# Sensor_Board.net
KiCad netlist of a schematic drawn in EAGLE
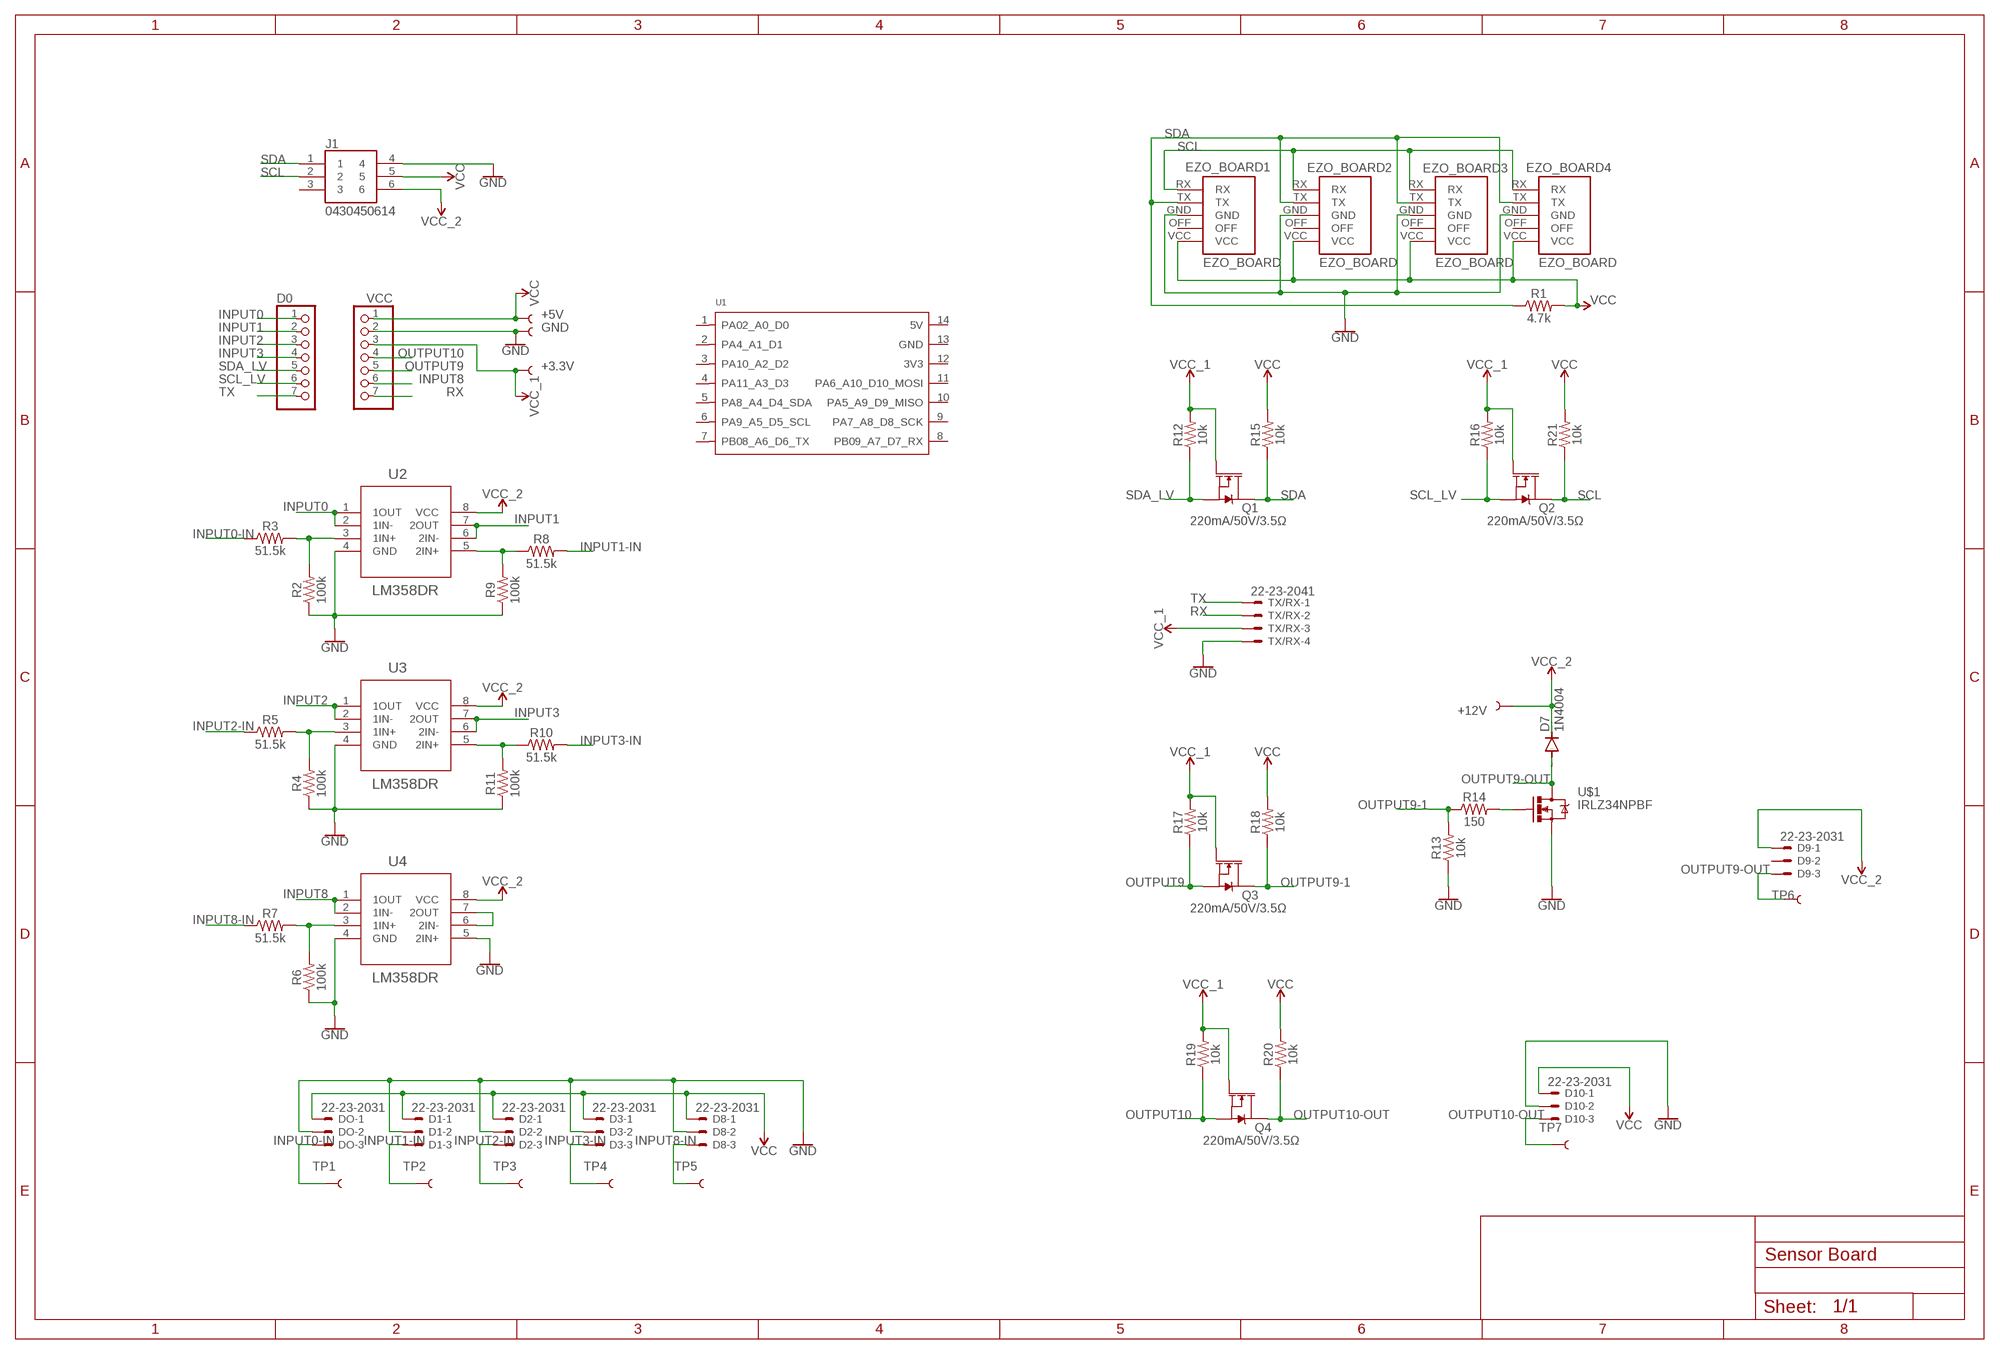
[diagram p0: schematic, sheet 1]

(export (version "E")
  (design (tool "Eeschema 10.0.6"))
  (components
    (comp (ref "+3.3V")
      (value "TEST-POINTPOGO_PTH")
      (footprint "eagle-import:1X01_NO_SILK")
      (libsource (lib "eagle-import") (part "TEST-POINTPOGO_PTH"))
    )
    (comp (ref "+5V")
      (value "TEST-POINTPOGO_PTH")
      (footprint "eagle-import:1X01_NO_SILK")
      (libsource (lib "eagle-import") (part "TEST-POINTPOGO_PTH"))
    )
    (comp (ref "+12V")
      (value "TEST-POINTPOGO_PTH")
      (footprint "eagle-import:1X01_NO_SILK")
      (libsource (lib "eagle-import") (part "TEST-POINTPOGO_PTH"))
    )
    (comp (ref "D0")
      (value "PINHD-1X7")
      (footprint "eagle-import:1X07")
      (libsource (lib "eagle-import") (part "PINHD-1X7"))
    )
    (comp (ref "D1")
      (value "22-23-2031")
      (footprint "eagle-import:22-23-2031")
      (fields (field (name "MF") "MOLEX"))
      (libsource (lib "eagle-import") (part "22-23-2031"))
    )
    (comp (ref "D2")
      (value "22-23-2031")
      (footprint "eagle-import:22-23-2031")
      (fields (field (name "MF") "MOLEX"))
      (libsource (lib "eagle-import") (part "22-23-2031"))
    )
    (comp (ref "D3")
      (value "22-23-2031")
      (footprint "eagle-import:22-23-2031")
      (fields (field (name "MF") "MOLEX"))
      (libsource (lib "eagle-import") (part "22-23-2031"))
    )
    (comp (ref "D7")
      (value "1N4004")
      (footprint "eagle-import:DO41-10")
      (libsource (lib "eagle-import") (part "1N4004"))
    )
    (comp (ref "D8")
      (value "22-23-2031")
      (footprint "eagle-import:22-23-2031")
      (fields (field (name "MF") "MOLEX"))
      (libsource (lib "eagle-import") (part "22-23-2031"))
    )
    (comp (ref "D9")
      (value "22-23-2031")
      (footprint "eagle-import:22-23-2031")
      (fields (field (name "MF") "MOLEX"))
      (libsource (lib "eagle-import") (part "22-23-2031"))
    )
    (comp (ref "D10")
      (value "22-23-2031")
      (footprint "eagle-import:22-23-2031")
      (fields (field (name "MF") "MOLEX"))
      (libsource (lib "eagle-import") (part "22-23-2031"))
    )
    (comp (ref "DO")
      (value "22-23-2031")
      (footprint "eagle-import:22-23-2031")
      (fields (field (name "MF") "MOLEX"))
      (libsource (lib "eagle-import") (part "22-23-2031"))
    )
    (comp (ref "EZO_BOARD1")
      (value "EZO_BOARD")
      (footprint "eagle-import:EZO_BOARD")
      (libsource (lib "eagle-import") (part "EZO_BOARD"))
    )
    (comp (ref "EZO_BOARD2")
      (value "EZO_BOARD")
      (footprint "eagle-import:EZO_BOARD")
      (libsource (lib "eagle-import") (part "EZO_BOARD"))
    )
    (comp (ref "EZO_BOARD3")
      (value "EZO_BOARD")
      (footprint "eagle-import:EZO_BOARD")
      (libsource (lib "eagle-import") (part "EZO_BOARD"))
    )
    (comp (ref "EZO_BOARD4")
      (value "EZO_BOARD")
      (footprint "eagle-import:EZO_BOARD")
      (libsource (lib "eagle-import") (part "EZO_BOARD"))
    )
    (comp (ref "GND")
      (value "TEST-POINTPOGO_PTH")
      (footprint "eagle-import:1X01_NO_SILK")
      (libsource (lib "eagle-import") (part "TEST-POINTPOGO_PTH"))
    )
    (comp (ref "J1")
      (value "0430450614")
      (footprint "eagle-import:MOLEX_0430450614")
      (fields (field (name "MF") "Molex"))
      (libsource (lib "eagle-import") (part "0430450614"))
    )
    (comp (ref "Q1")
      (value "220mA/50V/3.5Ω")
      (footprint "eagle-import:SOT23-3")
      (libsource (lib "eagle-import") (part "MOSFET-NCH-BSS138"))
    )
    (comp (ref "Q2")
      (value "220mA/50V/3.5Ω")
      (footprint "eagle-import:SOT23-3")
      (libsource (lib "eagle-import") (part "MOSFET-NCH-BSS138"))
    )
    (comp (ref "Q3")
      (value "220mA/50V/3.5Ω")
      (footprint "eagle-import:SOT23-3")
      (libsource (lib "eagle-import") (part "MOSFET-NCH-BSS138"))
    )
    (comp (ref "Q4")
      (value "220mA/50V/3.5Ω")
      (footprint "eagle-import:SOT23-3")
      (libsource (lib "eagle-import") (part "MOSFET-NCH-BSS138"))
    )
    (comp (ref "R1")
      (value "4.7k")
      (footprint "eagle-import:0603")
      (libsource (lib "eagle-import") (part "4.7KOHM-0603-1/10W-1%"))
    )
    (comp (ref "R2")
      (value "100k")
      (footprint "eagle-import:0603")
      (libsource (lib "eagle-import") (part "100KOHM-0603-1/10W-1%"))
    )
    (comp (ref "R3")
      (value "51.5k")
      (footprint "eagle-import:0603")
      (libsource (lib "eagle-import") (part "56KOHM"))
    )
    (comp (ref "R4")
      (value "100k")
      (footprint "eagle-import:0603")
      (libsource (lib "eagle-import") (part "100KOHM-0603-1/10W-1%"))
    )
    (comp (ref "R5")
      (value "51.5k")
      (footprint "eagle-import:0603")
      (libsource (lib "eagle-import") (part "56KOHM"))
    )
    (comp (ref "R6")
      (value "100k")
      (footprint "eagle-import:0603")
      (libsource (lib "eagle-import") (part "100KOHM-0603-1/10W-1%"))
    )
    (comp (ref "R7")
      (value "51.5k")
      (footprint "eagle-import:0603")
      (libsource (lib "eagle-import") (part "56KOHM"))
    )
    (comp (ref "R8")
      (value "51.5k")
      (footprint "eagle-import:0603")
      (libsource (lib "eagle-import") (part "56KOHM"))
    )
    (comp (ref "R9")
      (value "100k")
      (footprint "eagle-import:0603")
      (libsource (lib "eagle-import") (part "100KOHM-0603-1/10W-1%"))
    )
    (comp (ref "R10")
      (value "51.5k")
      (footprint "eagle-import:0603")
      (libsource (lib "eagle-import") (part "56KOHM"))
    )
    (comp (ref "R11")
      (value "100k")
      (footprint "eagle-import:0603")
      (libsource (lib "eagle-import") (part "100KOHM-0603-1/10W-1%"))
    )
    (comp (ref "R12")
      (value "10k")
      (footprint "eagle-import:0603")
      (libsource (lib "eagle-import") (part "10KOHM-0603-1/10W-1%"))
    )
    (comp (ref "R13")
      (value "10k")
      (footprint "eagle-import:0603")
      (libsource (lib "eagle-import") (part "10KOHM-0603-1/10W-1%"))
    )
    (comp (ref "R14")
      (value "150")
      (footprint "eagle-import:0603")
      (libsource (lib "eagle-import") (part "150OHM-0603-1/10W-1%"))
    )
    (comp (ref "R15")
      (value "10k")
      (footprint "eagle-import:0603")
      (libsource (lib "eagle-import") (part "10KOHM-0603-1/10W-1%"))
    )
    (comp (ref "R16")
      (value "10k")
      (footprint "eagle-import:0603")
      (libsource (lib "eagle-import") (part "10KOHM-0603-1/10W-1%"))
    )
    (comp (ref "R17")
      (value "10k")
      (footprint "eagle-import:0603")
      (libsource (lib "eagle-import") (part "10KOHM-0603-1/10W-1%"))
    )
    (comp (ref "R18")
      (value "10k")
      (footprint "eagle-import:0603")
      (libsource (lib "eagle-import") (part "10KOHM-0603-1/10W-1%"))
    )
    (comp (ref "R19")
      (value "10k")
      (footprint "eagle-import:0603")
      (libsource (lib "eagle-import") (part "10KOHM-0603-1/10W-1%"))
    )
    (comp (ref "R20")
      (value "10k")
      (footprint "eagle-import:0603")
      (libsource (lib "eagle-import") (part "10KOHM-0603-1/10W-1%"))
    )
    (comp (ref "R21")
      (value "10k")
      (footprint "eagle-import:0603")
      (libsource (lib "eagle-import") (part "10KOHM-0603-1/10W-1%"))
    )
    (comp (ref "TP1")
      (value "TEST-POINT2")
      (footprint "eagle-import:PAD.02X.02")
      (libsource (lib "eagle-import") (part "TEST-POINT2"))
    )
    (comp (ref "TP2")
      (value "TEST-POINT2")
      (footprint "eagle-import:PAD.02X.02")
      (libsource (lib "eagle-import") (part "TEST-POINT2"))
    )
    (comp (ref "TP3")
      (value "TEST-POINT2")
      (footprint "eagle-import:PAD.02X.02")
      (libsource (lib "eagle-import") (part "TEST-POINT2"))
    )
    (comp (ref "TP4")
      (value "TEST-POINT2")
      (footprint "eagle-import:PAD.02X.02")
      (libsource (lib "eagle-import") (part "TEST-POINT2"))
    )
    (comp (ref "TP5")
      (value "TEST-POINT2")
      (footprint "eagle-import:PAD.02X.02")
      (libsource (lib "eagle-import") (part "TEST-POINT2"))
    )
    (comp (ref "TP6")
      (value "TEST-POINT2")
      (footprint "eagle-import:PAD.02X.02")
      (libsource (lib "eagle-import") (part "TEST-POINT2"))
    )
    (comp (ref "TP7")
      (value "TEST-POINT2")
      (footprint "eagle-import:PAD.02X.02")
      (libsource (lib "eagle-import") (part "TEST-POINT2"))
    )
    (comp (ref "TX/RX")
      (value "22-23-2041")
      (footprint "eagle-import:22-23-2041")
      (fields (field (name "MF") "MOLEX"))
      (libsource (lib "eagle-import") (part "22-23-2041"))
    )
    (comp (ref "U$1")
      (value "IRLZ34NPBF")
      (footprint "eagle-import:TO-220(2)")
      (fields
        (field (name "DIGI-KEY_PART_NUMBER") "IRLZ34NPBF-ND")
        (field (name "MF") "Infineon Technologies")
      )
      (libsource (lib "eagle-import") (part "IRLZ34NPBF"))
    )
    (comp (ref "U1")
      (value "MOUDLE-SEEEDUINO-XIAO")
      (footprint "eagle-import:MOUDLE14P-2.54-21X17.8MM")
      (libsource (lib "eagle-import") (part "MOUDLE-SEEEDUINO-XIAO"))
    )
    (comp (ref "U2")
      (value "LM358DR")
      (footprint "eagle-import:D8")
      (fields (field (name "MANUFACTURER") "Texas Instruments"))
      (libsource (lib "eagle-import") (part "LM358DR"))
    )
    (comp (ref "U3")
      (value "LM358DR")
      (footprint "eagle-import:D8")
      (fields (field (name "MANUFACTURER") "Texas Instruments"))
      (libsource (lib "eagle-import") (part "LM358DR"))
    )
    (comp (ref "U4")
      (value "LM358DR")
      (footprint "eagle-import:D8")
      (fields (field (name "MANUFACTURER") "Texas Instruments"))
      (libsource (lib "eagle-import") (part "LM358DR"))
    )
    (comp (ref "VCC")
      (value "PINHD-1X7")
      (footprint "eagle-import:1X07")
      (libsource (lib "eagle-import") (part "PINHD-1X7"))
    )
  )
  (nets
    (net (code "1") (name "/INPUT0") (class "Default")
      (node (ref "D0") (pin "1") (pinfunction "1_1") (pintype "passive"))
      (node (ref "U2") (pin "1") (pinfunction "1OUT_1") (pintype "output"))
      (node (ref "U2") (pin "2") (pinfunction "1IN-_2") (pintype "input"))
    )
    (net (code "2") (name "/INPUT0-IN") (class "Default")
      (node (ref "DO") (pin "3") (pinfunction "S_3") (pintype "passive"))
      (node (ref "R3") (pin "1") (pinfunction "1_1") (pintype "passive"))
      (node (ref "TP1") (pin "1") (pinfunction "1_1") (pintype "bidirectional"))
    )
    (net (code "3") (name "/INPUT1") (class "Default")
      (node (ref "D0") (pin "2") (pinfunction "2_2") (pintype "passive"))
      (node (ref "U2") (pin "6") (pinfunction "2IN-_6") (pintype "input"))
      (node (ref "U2") (pin "7") (pinfunction "2OUT_7") (pintype "output"))
    )
    (net (code "4") (name "/INPUT1-IN") (class "Default")
      (node (ref "D1") (pin "3") (pinfunction "S_3") (pintype "passive"))
      (node (ref "R8") (pin "2") (pinfunction "2_2") (pintype "passive"))
      (node (ref "TP2") (pin "1") (pinfunction "1_1") (pintype "bidirectional"))
    )
    (net (code "5") (name "/INPUT2") (class "Default")
      (node (ref "D0") (pin "3") (pinfunction "3_3") (pintype "passive"))
      (node (ref "U3") (pin "1") (pinfunction "1OUT_1") (pintype "output"))
      (node (ref "U3") (pin "2") (pinfunction "1IN-_2") (pintype "input"))
    )
    (net (code "6") (name "/INPUT2-IN") (class "Default")
      (node (ref "D2") (pin "3") (pinfunction "S_3") (pintype "passive"))
      (node (ref "R5") (pin "1") (pinfunction "1_1") (pintype "passive"))
      (node (ref "TP3") (pin "1") (pinfunction "1_1") (pintype "bidirectional"))
    )
    (net (code "7") (name "/INPUT3") (class "Default")
      (node (ref "D0") (pin "4") (pinfunction "4_4") (pintype "passive"))
      (node (ref "U3") (pin "6") (pinfunction "2IN-_6") (pintype "input"))
      (node (ref "U3") (pin "7") (pinfunction "2OUT_7") (pintype "output"))
    )
    (net (code "8") (name "/INPUT3-IN") (class "Default")
      (node (ref "D3") (pin "3") (pinfunction "S_3") (pintype "passive"))
      (node (ref "R10") (pin "2") (pinfunction "2_2") (pintype "passive"))
      (node (ref "TP4") (pin "1") (pinfunction "1_1") (pintype "bidirectional"))
    )
    (net (code "9") (name "/INPUT8") (class "Default")
      (node (ref "U4") (pin "1") (pinfunction "1OUT_1") (pintype "output"))
      (node (ref "U4") (pin "2") (pinfunction "1IN-_2") (pintype "input"))
      (node (ref "VCC") (pin "6") (pinfunction "6_6") (pintype "passive"))
    )
    (net (code "10") (name "/INPUT8-IN") (class "Default")
      (node (ref "D8") (pin "3") (pinfunction "S_3") (pintype "passive"))
      (node (ref "R7") (pin "1") (pinfunction "1_1") (pintype "passive"))
      (node (ref "TP5") (pin "1") (pinfunction "1_1") (pintype "bidirectional"))
    )
    (net (code "11") (name "/OUTPUT9") (class "Default")
      (node (ref "Q3") (pin "2") (pinfunction "S_2") (pintype "bidirectional"))
      (node (ref "R17") (pin "1") (pinfunction "1_1") (pintype "passive"))
      (node (ref "VCC") (pin "5") (pinfunction "5_5") (pintype "passive"))
    )
    (net (code "12") (name "/OUTPUT9-1") (class "Default")
      (node (ref "Q3") (pin "3") (pinfunction "D_3") (pintype "bidirectional"))
      (node (ref "R13") (pin "2") (pinfunction "2_2") (pintype "passive"))
      (node (ref "R14") (pin "1") (pinfunction "1_1") (pintype "passive"))
      (node (ref "R18") (pin "1") (pinfunction "1_1") (pintype "passive"))
    )
    (net (code "13") (name "/OUTPUT9-OUT") (class "Default")
      (node (ref "D7") (pin "A") (pinfunction "A_A") (pintype "passive"))
      (node (ref "D9") (pin "3") (pinfunction "S_3") (pintype "passive"))
      (node (ref "TP6") (pin "1") (pinfunction "1_1") (pintype "bidirectional"))
      (node (ref "U$1") (pin "GND") (pinfunction "D_GND") (pintype "passive"))
    )
    (net (code "14") (name "/OUTPUT10") (class "Default")
      (node (ref "Q4") (pin "2") (pinfunction "S_2") (pintype "bidirectional"))
      (node (ref "R19") (pin "1") (pinfunction "1_1") (pintype "passive"))
      (node (ref "VCC") (pin "4") (pinfunction "4_4") (pintype "passive"))
    )
    (net (code "15") (name "/OUTPUT10-OUT") (class "Default")
      (node (ref "D10") (pin "3") (pinfunction "S_3") (pintype "passive"))
      (node (ref "Q4") (pin "3") (pinfunction "D_3") (pintype "bidirectional"))
      (node (ref "R20") (pin "1") (pinfunction "1_1") (pintype "passive"))
      (node (ref "TP7") (pin "1") (pinfunction "1_1") (pintype "bidirectional"))
    )
    (net (code "16") (name "/RX") (class "Default")
      (node (ref "TX/RX") (pin "2") (pinfunction "S_2") (pintype "passive"))
      (node (ref "VCC") (pin "7") (pinfunction "7_7") (pintype "passive"))
    )
    (net (code "17") (name "/SCL") (class "Default")
      (node (ref "EZO_BOARD1") (pin "RX") (pinfunction "RX_RX") (pintype "bidirectional"))
      (node (ref "EZO_BOARD2") (pin "RX") (pinfunction "RX_RX") (pintype "bidirectional"))
      (node (ref "EZO_BOARD3") (pin "RX") (pinfunction "RX_RX") (pintype "bidirectional"))
      (node (ref "EZO_BOARD4") (pin "RX") (pinfunction "RX_RX") (pintype "bidirectional"))
      (node (ref "J1") (pin "2") (pinfunction "2_2") (pintype "passive"))
      (node (ref "Q2") (pin "3") (pinfunction "D_3") (pintype "bidirectional"))
      (node (ref "R21") (pin "1") (pinfunction "1_1") (pintype "passive"))
    )
    (net (code "18") (name "/SCL_LV") (class "Default")
      (node (ref "D0") (pin "6") (pinfunction "6_6") (pintype "passive"))
      (node (ref "Q2") (pin "2") (pinfunction "S_2") (pintype "bidirectional"))
      (node (ref "R16") (pin "1") (pinfunction "1_1") (pintype "passive"))
    )
    (net (code "19") (name "/SDA") (class "Default")
      (node (ref "EZO_BOARD1") (pin "TX") (pinfunction "TX_TX") (pintype "bidirectional"))
      (node (ref "EZO_BOARD2") (pin "TX") (pinfunction "TX_TX") (pintype "bidirectional"))
      (node (ref "EZO_BOARD3") (pin "TX") (pinfunction "TX_TX") (pintype "bidirectional"))
      (node (ref "EZO_BOARD4") (pin "TX") (pinfunction "TX_TX") (pintype "bidirectional"))
      (node (ref "J1") (pin "1") (pinfunction "1_1") (pintype "passive"))
      (node (ref "Q1") (pin "3") (pinfunction "D_3") (pintype "bidirectional"))
      (node (ref "R1") (pin "1") (pinfunction "1_1") (pintype "passive"))
      (node (ref "R15") (pin "1") (pinfunction "1_1") (pintype "passive"))
    )
    (net (code "20") (name "/SDA_LV") (class "Default")
      (node (ref "D0") (pin "5") (pinfunction "5_5") (pintype "passive"))
      (node (ref "Q1") (pin "2") (pinfunction "S_2") (pintype "bidirectional"))
      (node (ref "R12") (pin "1") (pinfunction "1_1") (pintype "passive"))
    )
    (net (code "21") (name "/TX") (class "Default")
      (node (ref "D0") (pin "7") (pinfunction "7_7") (pintype "passive"))
      (node (ref "TX/RX") (pin "1") (pinfunction "S_1") (pintype "passive"))
    )
    (net (code "22") (name "GND") (class "Default")
      (node (ref "D1") (pin "2") (pinfunction "S_2") (pintype "passive"))
      (node (ref "D10") (pin "2") (pinfunction "S_2") (pintype "passive"))
      (node (ref "D2") (pin "2") (pinfunction "S_2") (pintype "passive"))
      (node (ref "D3") (pin "2") (pinfunction "S_2") (pintype "passive"))
      (node (ref "D8") (pin "2") (pinfunction "S_2") (pintype "passive"))
      (node (ref "DO") (pin "2") (pinfunction "S_2") (pintype "passive"))
      (node (ref "EZO_BOARD1") (pin "GND") (pinfunction "GND_GND") (pintype "bidirectional"))
      (node (ref "EZO_BOARD2") (pin "GND") (pinfunction "GND_GND") (pintype "bidirectional"))
      (node (ref "EZO_BOARD3") (pin "GND") (pinfunction "GND_GND") (pintype "bidirectional"))
      (node (ref "EZO_BOARD4") (pin "GND") (pinfunction "GND_GND") (pintype "bidirectional"))
      (node (ref "GND") (pin "1") (pinfunction "1_1") (pintype "bidirectional"))
      (node (ref "J1") (pin "4") (pinfunction "4_4") (pintype "passive"))
      (node (ref "R11") (pin "1") (pinfunction "1_1") (pintype "passive"))
      (node (ref "R13") (pin "1") (pinfunction "1_1") (pintype "passive"))
      (node (ref "R2") (pin "1") (pinfunction "1_1") (pintype "passive"))
      (node (ref "R4") (pin "1") (pinfunction "1_1") (pintype "passive"))
      (node (ref "R6") (pin "1") (pinfunction "1_1") (pintype "passive"))
      (node (ref "R9") (pin "1") (pinfunction "1_1") (pintype "passive"))
      (node (ref "TX/RX") (pin "4") (pinfunction "S_4") (pintype "passive"))
      (node (ref "U$1") (pin "OUT") (pinfunction "S_OUT") (pintype "passive"))
      (node (ref "U2") (pin "4") (pinfunction "GND_4") (pintype "power_in"))
      (node (ref "U3") (pin "4") (pinfunction "GND_4") (pintype "power_in"))
      (node (ref "U4") (pin "4") (pinfunction "GND_4") (pintype "power_in"))
      (node (ref "U4") (pin "5") (pinfunction "2IN+_5") (pintype "input"))
      (node (ref "VCC") (pin "2") (pinfunction "2_2") (pintype "passive"))
    )
    (net (code "23") (name "Net-(U$1-G)") (class "Default")
      (node (ref "R14") (pin "2") (pinfunction "2_2") (pintype "passive"))
      (node (ref "U$1") (pin "IN") (pinfunction "G_IN") (pintype "passive"))
    )
    (net (code "24") (name "Net-(U2-1IN+)") (class "Default")
      (node (ref "R2") (pin "2") (pinfunction "2_2") (pintype "passive"))
      (node (ref "R3") (pin "2") (pinfunction "2_2") (pintype "passive"))
      (node (ref "U2") (pin "3") (pinfunction "1IN+_3") (pintype "input"))
    )
    (net (code "25") (name "Net-(U2-2IN+)") (class "Default")
      (node (ref "R8") (pin "1") (pinfunction "1_1") (pintype "passive"))
      (node (ref "R9") (pin "2") (pinfunction "2_2") (pintype "passive"))
      (node (ref "U2") (pin "5") (pinfunction "2IN+_5") (pintype "input"))
    )
    (net (code "26") (name "Net-(U3-1IN+)") (class "Default")
      (node (ref "R4") (pin "2") (pinfunction "2_2") (pintype "passive"))
      (node (ref "R5") (pin "2") (pinfunction "2_2") (pintype "passive"))
      (node (ref "U3") (pin "3") (pinfunction "1IN+_3") (pintype "input"))
    )
    (net (code "27") (name "Net-(U3-2IN+)") (class "Default")
      (node (ref "R10") (pin "1") (pinfunction "1_1") (pintype "passive"))
      (node (ref "R11") (pin "2") (pinfunction "2_2") (pintype "passive"))
      (node (ref "U3") (pin "5") (pinfunction "2IN+_5") (pintype "input"))
    )
    (net (code "28") (name "Net-(U4-1IN+)") (class "Default")
      (node (ref "R6") (pin "2") (pinfunction "2_2") (pintype "passive"))
      (node (ref "R7") (pin "2") (pinfunction "2_2") (pintype "passive"))
      (node (ref "U4") (pin "3") (pinfunction "1IN+_3") (pintype "input"))
    )
    (net (code "29") (name "Net-(U4-2IN-)") (class "Default")
      (node (ref "U4") (pin "6") (pinfunction "2IN-_6") (pintype "input"))
      (node (ref "U4") (pin "7") (pinfunction "2OUT_7") (pintype "output"))
    )
    (net (code "30") (name "VCC") (class "Default")
      (node (ref "+5V") (pin "1") (pinfunction "1_1") (pintype "bidirectional"))
      (node (ref "D1") (pin "1") (pinfunction "S_1") (pintype "passive"))
      (node (ref "D10") (pin "1") (pinfunction "S_1") (pintype "passive"))
      (node (ref "D2") (pin "1") (pinfunction "S_1") (pintype "passive"))
      (node (ref "D3") (pin "1") (pinfunction "S_1") (pintype "passive"))
      (node (ref "D8") (pin "1") (pinfunction "S_1") (pintype "passive"))
      (node (ref "DO") (pin "1") (pinfunction "S_1") (pintype "passive"))
      (node (ref "EZO_BOARD1") (pin "VCC") (pinfunction "VCC_VCC") (pintype "bidirectional"))
      (node (ref "EZO_BOARD2") (pin "VCC") (pinfunction "VCC_VCC") (pintype "bidirectional"))
      (node (ref "EZO_BOARD3") (pin "VCC") (pinfunction "VCC_VCC") (pintype "bidirectional"))
      (node (ref "EZO_BOARD4") (pin "VCC") (pinfunction "VCC_VCC") (pintype "bidirectional"))
      (node (ref "J1") (pin "5") (pinfunction "5_5") (pintype "passive"))
      (node (ref "R1") (pin "2") (pinfunction "2_2") (pintype "passive"))
      (node (ref "R15") (pin "2") (pinfunction "2_2") (pintype "passive"))
      (node (ref "R18") (pin "2") (pinfunction "2_2") (pintype "passive"))
      (node (ref "R20") (pin "2") (pinfunction "2_2") (pintype "passive"))
      (node (ref "R21") (pin "2") (pinfunction "2_2") (pintype "passive"))
      (node (ref "VCC") (pin "1") (pinfunction "1_1") (pintype "passive"))
    )
    (net (code "31") (name "VCC_1") (class "Default")
      (node (ref "+3.3V") (pin "1") (pinfunction "1_1") (pintype "bidirectional"))
      (node (ref "Q1") (pin "1") (pinfunction "G_1") (pintype "bidirectional"))
      (node (ref "Q2") (pin "1") (pinfunction "G_1") (pintype "bidirectional"))
      (node (ref "Q3") (pin "1") (pinfunction "G_1") (pintype "bidirectional"))
      (node (ref "Q4") (pin "1") (pinfunction "G_1") (pintype "bidirectional"))
      (node (ref "R12") (pin "2") (pinfunction "2_2") (pintype "passive"))
      (node (ref "R16") (pin "2") (pinfunction "2_2") (pintype "passive"))
      (node (ref "R17") (pin "2") (pinfunction "2_2") (pintype "passive"))
      (node (ref "R19") (pin "2") (pinfunction "2_2") (pintype "passive"))
      (node (ref "TX/RX") (pin "3") (pinfunction "S_3") (pintype "passive"))
      (node (ref "VCC") (pin "3") (pinfunction "3_3") (pintype "passive"))
    )
    (net (code "32") (name "VCC_2") (class "Default")
      (node (ref "+12V") (pin "1") (pinfunction "1_1") (pintype "bidirectional"))
      (node (ref "D7") (pin "C") (pinfunction "C_C") (pintype "passive"))
      (node (ref "D9") (pin "1") (pinfunction "S_1") (pintype "passive"))
      (node (ref "J1") (pin "6") (pinfunction "6_6") (pintype "passive"))
      (node (ref "U2") (pin "8") (pinfunction "VCC_8") (pintype "power_in"))
      (node (ref "U3") (pin "8") (pinfunction "VCC_8") (pintype "power_in"))
      (node (ref "U4") (pin "8") (pinfunction "VCC_8") (pintype "power_in"))
    )
    (net (code "33") (name "unconnected-(D9B-S-Pad2)") (class "Default")
      (node (ref "D9") (pin "2") (pinfunction "S_2") (pintype "passive"))
    )
    (net (code "34") (name "unconnected-(EZO_BOARD1-PadOFF)") (class "Default")
      (node (ref "EZO_BOARD1") (pin "OFF") (pinfunction "OFF_OFF") (pintype "bidirectional"))
    )
    (net (code "35") (name "unconnected-(EZO_BOARD2-PadOFF)") (class "Default")
      (node (ref "EZO_BOARD2") (pin "OFF") (pinfunction "OFF_OFF") (pintype "bidirectional"))
    )
    (net (code "36") (name "unconnected-(EZO_BOARD3-PadOFF)") (class "Default")
      (node (ref "EZO_BOARD3") (pin "OFF") (pinfunction "OFF_OFF") (pintype "bidirectional"))
    )
    (net (code "37") (name "unconnected-(EZO_BOARD4-PadOFF)") (class "Default")
      (node (ref "EZO_BOARD4") (pin "OFF") (pinfunction "OFF_OFF") (pintype "bidirectional"))
    )
    (net (code "38") (name "unconnected-(J1-Pad3)") (class "Default")
      (node (ref "J1") (pin "3") (pinfunction "3_3") (pintype "passive"))
    )
    (net (code "39") (name "unconnected-(U1-3V3-Pad12)") (class "Default")
      (node (ref "U1") (pin "12") (pinfunction "3V3_12") (pintype "bidirectional"))
    )
    (net (code "40") (name "unconnected-(U1-5V-Pad14)") (class "Default")
      (node (ref "U1") (pin "14") (pinfunction "5V_14") (pintype "bidirectional"))
    )
    (net (code "41") (name "unconnected-(U1-GND-Pad13)") (class "Default")
      (node (ref "U1") (pin "13") (pinfunction "GND_13") (pintype "bidirectional"))
    )
    (net (code "42") (name "unconnected-(U1-PA02_A0_D0-Pad1)") (class "Default")
      (node (ref "U1") (pin "1") (pinfunction "PA02_A0_D0_1") (pintype "bidirectional"))
    )
    (net (code "43") (name "unconnected-(U1-PA4_A1_D1-Pad2)") (class "Default")
      (node (ref "U1") (pin "2") (pinfunction "PA4_A1_D1_2") (pintype "bidirectional"))
    )
    (net (code "44") (name "unconnected-(U1-PA5_A9_D9_MISO-Pad10)") (class "Default")
      (node (ref "U1") (pin "10") (pinfunction "PA5_A9_D9_MISO_10") (pintype "bidirectional"))
    )
    (net (code "45") (name "unconnected-(U1-PA6_A10_D10_MOSI-Pad11)") (class "Default")
      (node (ref "U1") (pin "11") (pinfunction "PA6_A10_D10_MOSI_11") (pintype "bidirectional"))
    )
    (net (code "46") (name "unconnected-(U1-PA7_A8_D8_SCK-Pad9)") (class "Default")
      (node (ref "U1") (pin "9") (pinfunction "PA7_A8_D8_SCK_9") (pintype "bidirectional"))
    )
    (net (code "47") (name "unconnected-(U1-PA8_A4_D4_SDA-Pad5)") (class "Default")
      (node (ref "U1") (pin "5") (pinfunction "PA8_A4_D4_SDA_5") (pintype "bidirectional"))
    )
    (net (code "48") (name "unconnected-(U1-PA9_A5_D5_SCL-Pad6)") (class "Default")
      (node (ref "U1") (pin "6") (pinfunction "PA9_A5_D5_SCL_6") (pintype "bidirectional"))
    )
    (net (code "49") (name "unconnected-(U1-PA10_A2_D2-Pad3)") (class "Default")
      (node (ref "U1") (pin "3") (pinfunction "PA10_A2_D2_3") (pintype "bidirectional"))
    )
    (net (code "50") (name "unconnected-(U1-PA11_A3_D3-Pad4)") (class "Default")
      (node (ref "U1") (pin "4") (pinfunction "PA11_A3_D3_4") (pintype "bidirectional"))
    )
    (net (code "51") (name "unconnected-(U1-PB08_A6_D6_TX-Pad7)") (class "Default")
      (node (ref "U1") (pin "7") (pinfunction "PB08_A6_D6_TX_7") (pintype "bidirectional"))
    )
    (net (code "52") (name "unconnected-(U1-PB09_A7_D7_RX-Pad8)") (class "Default")
      (node (ref "U1") (pin "8") (pinfunction "PB09_A7_D7_RX_8") (pintype "bidirectional"))
    )
  )
)
